# Relay_ClockLed.net
KiCad netlist of a schematic drawn in Altium Designer
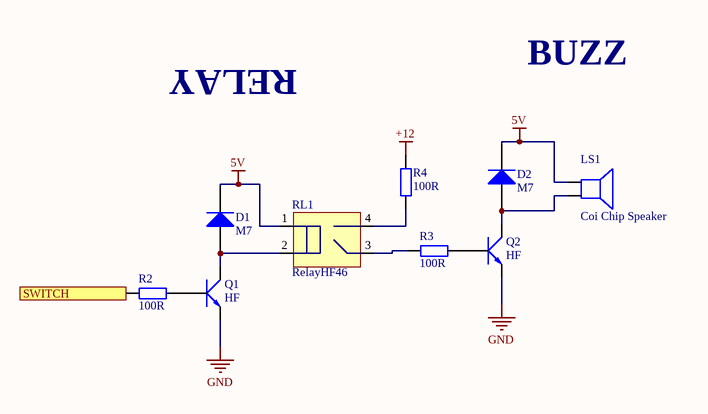
[diagram p0: Relay_ClockLed.SchDoc]

(export (version "E")
  (design (tool "Eeschema 10.0.6"))
  (components
    (comp (ref "D1")
      (value "M7")
      (footprint "DIODE SMA")
      (description "Dán")
      (libsource (lib "Altium_Lib_by_KhueNguyenCreator") (part "Diode M7 ( 4007 )"))
    )
    (comp (ref "D2")
      (value "M7")
      (footprint "DIODE SMA")
      (description "Dán")
      (libsource (lib "Altium_Lib_by_KhueNguyenCreator") (part "Diode M7 ( 4007 )"))
    )
    (comp (ref "LS1")
      (value "Coi Chip Speaker")
      (footprint "Coi Chip Speacker")
      (description "Còi chip")
      (libsource (lib "Altium_Lib_by_KhueNguyenCreator") (part "Coi Chip Speaker"))
    )
    (comp (ref "Q1")
      (value "HF")
      (footprint "SOT23")
      (description "NPN transistor")
      (libsource (lib "Altium_Lib_by_KhueNguyenCreator") (part "C1815 HF SMD"))
    )
    (comp (ref "Q2")
      (value "HF")
      (footprint "SOT23")
      (description "NPN transistor")
      (libsource (lib "Altium_Lib_by_KhueNguyenCreator") (part "C1815 HF SMD"))
    )
    (comp (ref "R2")
      (value "100R")
      (footprint "tro smd 0805")
      (description "Dán")
      (libsource (lib "Altium_Lib_by_KhueNguyenCreator") (part "Tro 0805 5% 100R"))
    )
    (comp (ref "R3")
      (value "100R")
      (footprint "tro smd 0805")
      (description "Dán")
      (libsource (lib "Altium_Lib_by_KhueNguyenCreator") (part "Tro 0805 5% 100R"))
    )
    (comp (ref "R4")
      (value "100R")
      (footprint "tro smd 0805")
      (description "Dán")
      (libsource (lib "Altium_Lib_by_KhueNguyenCreator") (part "Tro 0805 5% 100R"))
    )
    (comp (ref "RL1")
      (value "RelayHF46")
      (footprint "Relay 4 chan HF46F")
      (description "Relay 4 chan HF46F")
      (libsource (lib "Altium_Lib_by_KhueNguyenCreator") (part "Relay 4 chan HF46F"))
    )
  )
  (nets
    (net (code "1") (name "+12") (class "Default")
      (node (ref "R4") (pin "2") (pinfunction "2_2") (pintype "passive"))
    )
    (net (code "2") (name "/SWITCH") (class "Default")
      (node (ref "R2") (pin "1") (pinfunction "1_1") (pintype "passive"))
    )
    (net (code "3") (name "5V") (class "Default")
      (node (ref "D1") (pin "2") (pinfunction "K_2") (pintype "passive"))
      (node (ref "D2") (pin "2") (pinfunction "K_2") (pintype "passive"))
      (node (ref "LS1") (pin "1") (pinfunction "1_1") (pintype "passive"))
      (node (ref "RL1") (pin "1") (pintype "passive"))
    )
    (net (code "4") (name "GND") (class "Default")
      (node (ref "Q1") (pin "2") (pinfunction "E_2") (pintype "passive"))
      (node (ref "Q2") (pin "2") (pinfunction "E_2") (pintype "passive"))
    )
    (net (code "5") (name "Net-(D1-A)") (class "Default")
      (node (ref "D1") (pin "1") (pinfunction "A_1") (pintype "passive"))
      (node (ref "Q1") (pin "3") (pinfunction "C_3") (pintype "passive"))
      (node (ref "RL1") (pin "2") (pintype "passive"))
    )
    (net (code "6") (name "Net-(D2-A)") (class "Default")
      (node (ref "D2") (pin "1") (pinfunction "A_1") (pintype "passive"))
      (node (ref "LS1") (pin "2") (pinfunction "2_2") (pintype "passive"))
      (node (ref "Q2") (pin "3") (pinfunction "C_3") (pintype "passive"))
    )
    (net (code "7") (name "Net-(Q1-B)") (class "Default")
      (node (ref "Q1") (pin "1") (pinfunction "B_1") (pintype "passive"))
      (node (ref "R2") (pin "2") (pinfunction "2_2") (pintype "passive"))
    )
    (net (code "8") (name "Net-(Q2-B)") (class "Default")
      (node (ref "Q2") (pin "1") (pinfunction "B_1") (pintype "passive"))
      (node (ref "R3") (pin "2") (pinfunction "2_2") (pintype "passive"))
    )
    (net (code "9") (name "Net-(R3-Pad1)") (class "Default")
      (node (ref "R3") (pin "1") (pinfunction "1_1") (pintype "passive"))
      (node (ref "RL1") (pin "3") (pinfunction "AC/DC_3") (pintype "passive"))
    )
    (net (code "10") (name "Net-(R4-Pad1)") (class "Default")
      (node (ref "R4") (pin "1") (pinfunction "1_1") (pintype "passive"))
      (node (ref "RL1") (pin "4") (pinfunction "AC/DC_4") (pintype "passive"))
    )
  )
)
